# Adafruit_QMC5883P_Magnetometer.net
KiCad netlist of a schematic drawn in EAGLE
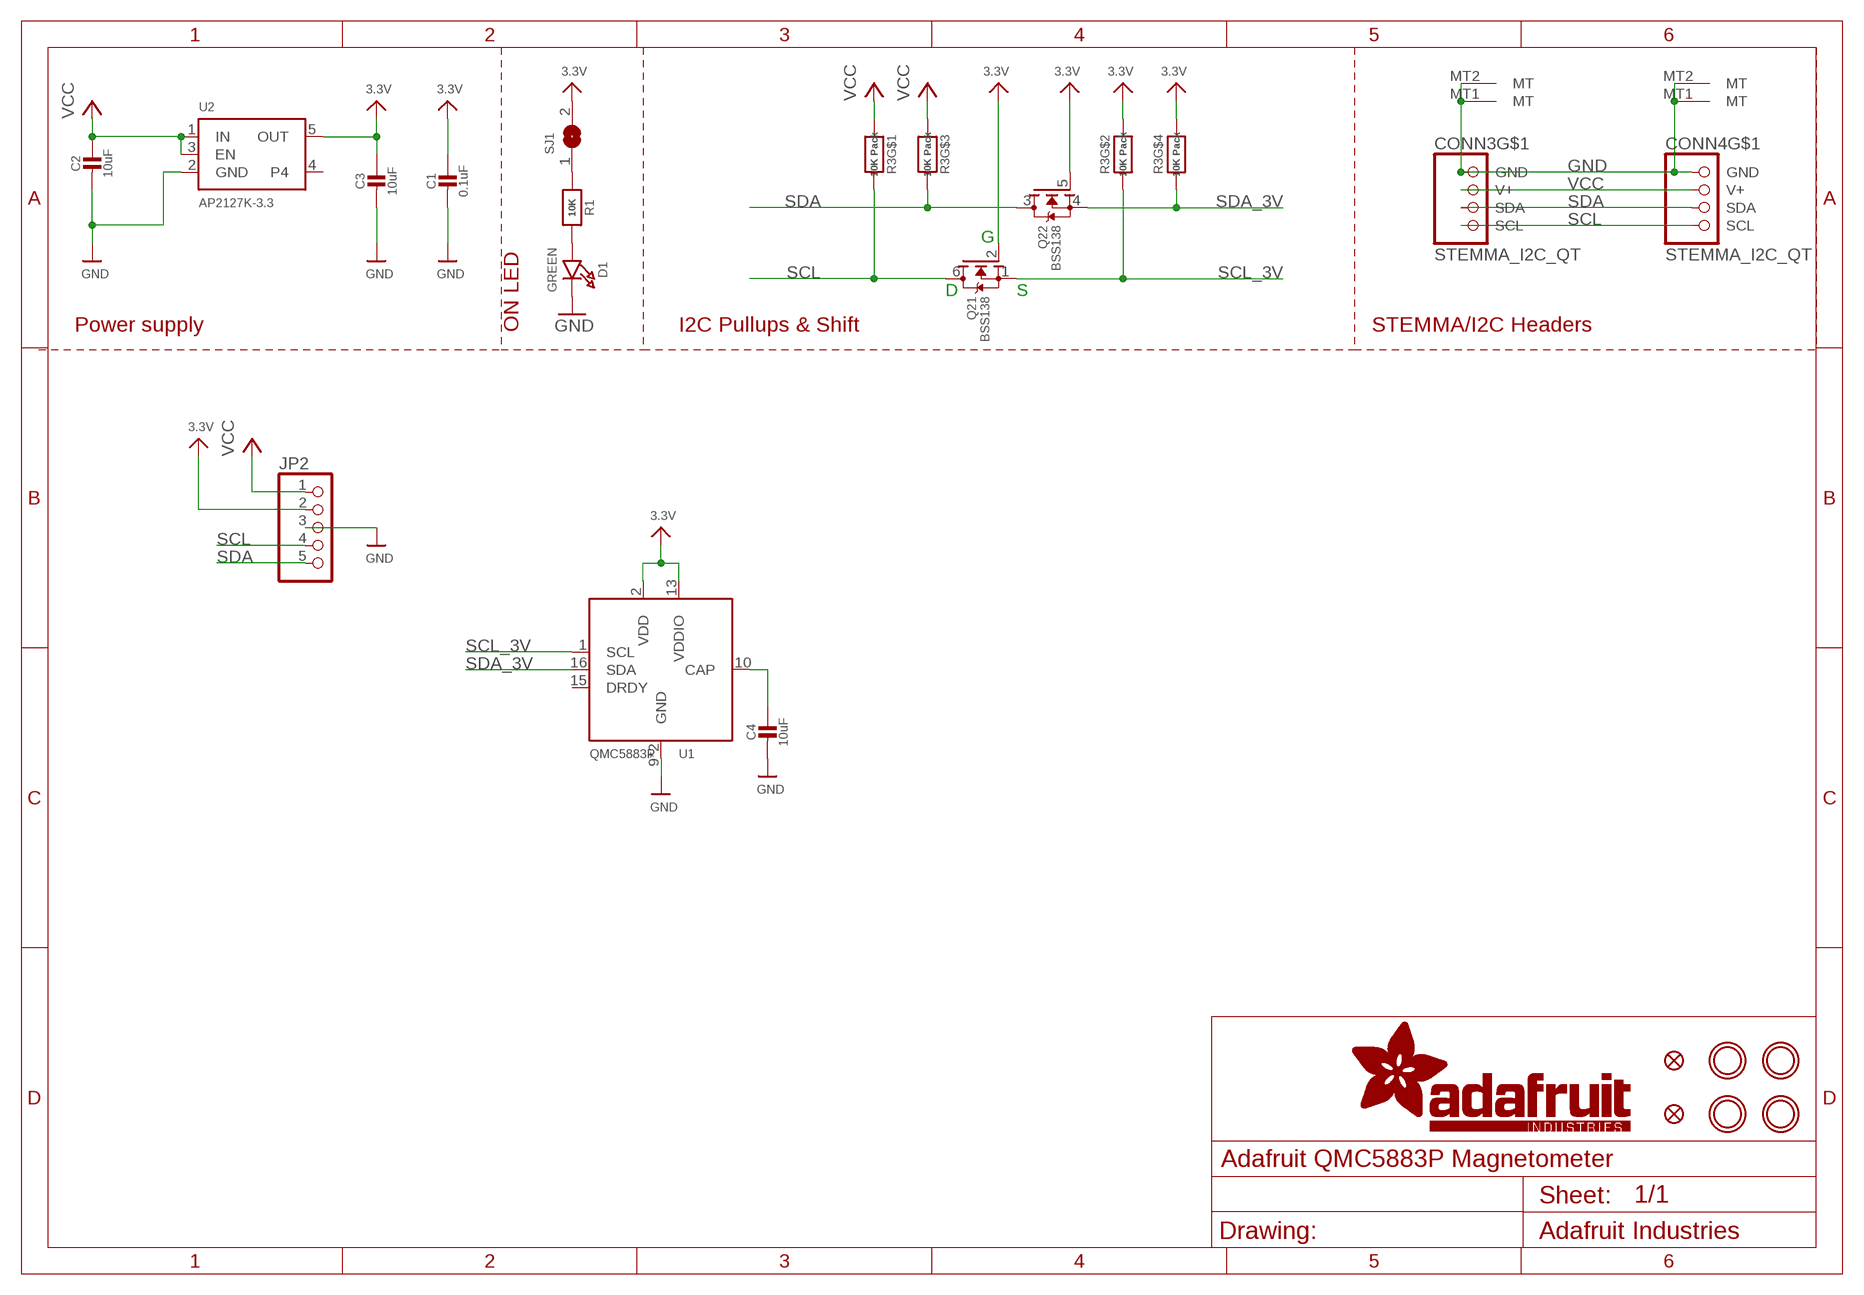
[diagram p0: schematic, sheet 1]

(export (version "E")
  (design (tool "Eeschema 10.0.6"))
  (components
    (comp (ref "C1")
      (value "0.1uF")
      (footprint "eagle-import:0603-NO")
      (libsource (lib "eagle-import") (part "CAP_CERAMIC0603_NO"))
    )
    (comp (ref "C2")
      (value "10uF")
      (footprint "eagle-import:0805-NO")
      (libsource (lib "eagle-import") (part "CAP_CERAMIC0805-NOOUTLINE"))
    )
    (comp (ref "C3")
      (value "10uF")
      (footprint "eagle-import:0805-NO")
      (libsource (lib "eagle-import") (part "CAP_CERAMIC0805-NOOUTLINE"))
    )
    (comp (ref "C4")
      (value "10uF")
      (footprint "eagle-import:0805-NO")
      (libsource (lib "eagle-import") (part "CAP_CERAMIC0805-NOOUTLINE"))
    )
    (comp (ref "CONN3")
      (value "STEMMA_I2C_QT")
      (footprint "eagle-import:JST_SH4")
      (libsource (lib "eagle-import") (part "STEMMA_I2C_QT"))
    )
    (comp (ref "CONN4")
      (value "STEMMA_I2C_QT")
      (footprint "eagle-import:JST_SH4")
      (libsource (lib "eagle-import") (part "STEMMA_I2C_QT"))
    )
    (comp (ref "D1")
      (value "GREEN")
      (footprint "eagle-import:CHIPLED_0603_NOOUTLINE")
      (libsource (lib "eagle-import") (part "LED0603_NOOUTLINE"))
    )
    (comp (ref "FID3")
      (value "FIDUCIAL_0.5MM")
      (footprint "eagle-import:FIDUCIAL_0.5MM")
      (libsource (lib "eagle-import") (part "FIDUCIAL_0.5MM"))
    )
    (comp (ref "FID4")
      (value "FIDUCIAL_0.5MM")
      (footprint "eagle-import:FIDUCIAL_0.5MM")
      (libsource (lib "eagle-import") (part "FIDUCIAL_0.5MM"))
    )
    (comp (ref "JP2")
      (value "HEADER-1X570MIL")
      (footprint "eagle-import:1X05_ROUND_70")
      (libsource (lib "eagle-import") (part "HEADER-1X570MIL"))
    )
    (comp (ref "Q2")
      (value "BSS138")
      (footprint "eagle-import:SOT363")
      (libsource (lib "eagle-import") (part "MOSFET-N_DUAL"))
    )
    (comp (ref "R1")
      (value "10K")
      (footprint "eagle-import:0603-NO")
      (libsource (lib "eagle-import") (part "RESISTOR_0603_NOOUT"))
    )
    (comp (ref "R3")
      (value "10K Pack")
      (footprint "eagle-import:RESPACK_4X0603")
      (libsource (lib "eagle-import") (part "RESISTOR_4PACK"))
    )
    (comp (ref "SJ1")
      (value "SOLDERJUMPERCLOSED")
      (footprint "eagle-import:SOLDERJUMPER_CLOSEDWIRE")
      (libsource (lib "eagle-import") (part "SOLDERJUMPERCLOSED"))
    )
    (comp (ref "U$1")
      (value "MOUNTINGHOLE2.5")
      (footprint "eagle-import:MOUNTINGHOLE_2.5_PLATED")
      (libsource (lib "eagle-import") (part "MOUNTINGHOLE2.5"))
    )
    (comp (ref "U$17")
      (value "MOUNTINGHOLE2.5")
      (footprint "eagle-import:MOUNTINGHOLE_2.5_PLATED")
      (libsource (lib "eagle-import") (part "MOUNTINGHOLE2.5"))
    )
    (comp (ref "U$19")
      (value "MOUNTINGHOLE2.5")
      (footprint "eagle-import:MOUNTINGHOLE_2.5_PLATED")
      (libsource (lib "eagle-import") (part "MOUNTINGHOLE2.5"))
    )
    (comp (ref "U$21")
      (value "MOUNTINGHOLE2.5")
      (footprint "eagle-import:MOUNTINGHOLE_2.5_PLATED")
      (libsource (lib "eagle-import") (part "MOUNTINGHOLE2.5"))
    )
    (comp (ref "U1")
      (value "QMC5883P")
      (footprint "eagle-import:HMC5883L")
      (libsource (lib "eagle-import") (part "MMC5883MA"))
    )
    (comp (ref "U2")
      (value "AP2127K-3.3")
      (footprint "eagle-import:SOT23-5")
      (libsource (lib "eagle-import") (part "VREG_SOT23-5"))
    )
  )
  (nets
    (net (code "1") (name "/SCL") (class "Default")
      (node (ref "CONN3") (pin "4") (pinfunction "SCL_4") (pintype "passive"))
      (node (ref "CONN4") (pin "4") (pinfunction "SCL_4") (pintype "passive"))
      (node (ref "JP2") (pin "4") (pinfunction "4_4") (pintype "passive"))
      (node (ref "Q2") (pin "6") (pinfunction "D_6") (pintype "bidirectional"))
      (node (ref "R3") (pin "8") (pinfunction "2_8") (pintype "passive"))
    )
    (net (code "2") (name "/SCL_3V") (class "Default")
      (node (ref "Q2") (pin "1") (pinfunction "S_1") (pintype "bidirectional"))
      (node (ref "R3") (pin "7") (pinfunction "2_7") (pintype "passive"))
      (node (ref "U1") (pin "1") (pinfunction "SCL_1") (pintype "bidirectional"))
    )
    (net (code "3") (name "/SDA") (class "Default")
      (node (ref "CONN3") (pin "3") (pinfunction "SDA_3") (pintype "passive"))
      (node (ref "CONN4") (pin "3") (pinfunction "SDA_3") (pintype "passive"))
      (node (ref "JP2") (pin "5") (pinfunction "5_5") (pintype "passive"))
      (node (ref "Q2") (pin "3") (pinfunction "D_3") (pintype "bidirectional"))
      (node (ref "R3") (pin "6") (pinfunction "2_6") (pintype "passive"))
    )
    (net (code "4") (name "/SDA_3V") (class "Default")
      (node (ref "Q2") (pin "4") (pinfunction "S_4") (pintype "bidirectional"))
      (node (ref "R3") (pin "5") (pinfunction "2_5") (pintype "passive"))
      (node (ref "U1") (pin "16") (pinfunction "SDA_16") (pintype "bidirectional"))
    )
    (net (code "5") (name "3.3V") (class "Default")
      (node (ref "C1") (pin "1") (pinfunction "1_1") (pintype "passive"))
      (node (ref "C3") (pin "1") (pinfunction "1_1") (pintype "passive"))
      (node (ref "JP2") (pin "2") (pinfunction "2_2") (pintype "passive"))
      (node (ref "Q2") (pin "2") (pinfunction "G_2") (pintype "bidirectional"))
      (node (ref "Q2") (pin "5") (pinfunction "G_5") (pintype "bidirectional"))
      (node (ref "R3") (pin "2") (pinfunction "1_2") (pintype "passive"))
      (node (ref "R3") (pin "4") (pinfunction "1_4") (pintype "passive"))
      (node (ref "SJ1") (pin "2") (pinfunction "2_2") (pintype "passive"))
      (node (ref "U1") (pin "13") (pinfunction "VDDIO_13") (pintype "power_in"))
      (node (ref "U1") (pin "2") (pinfunction "VDD_2") (pintype "power_in"))
      (node (ref "U2") (pin "5") (pinfunction "OUT_5") (pintype "power_in"))
    )
    (net (code "6") (name "GND") (class "Default")
      (node (ref "C1") (pin "2") (pinfunction "2_2") (pintype "passive"))
      (node (ref "C2") (pin "2") (pinfunction "2_2") (pintype "passive"))
      (node (ref "C3") (pin "2") (pinfunction "2_2") (pintype "passive"))
      (node (ref "C4") (pin "2") (pinfunction "2_2") (pintype "passive"))
      (node (ref "CONN3") (pin "1") (pinfunction "GND_1") (pintype "passive"))
      (node (ref "CONN3") (pin "MT1") (pinfunction "MT_MT1") (pintype "bidirectional"))
      (node (ref "CONN3") (pin "MT2") (pinfunction "MT_MT2") (pintype "bidirectional"))
      (node (ref "CONN4") (pin "1") (pinfunction "GND_1") (pintype "passive"))
      (node (ref "CONN4") (pin "MT1") (pinfunction "MT_MT1") (pintype "bidirectional"))
      (node (ref "CONN4") (pin "MT2") (pinfunction "MT_MT2") (pintype "bidirectional"))
      (node (ref "D1") (pin "C") (pinfunction "C_C") (pintype "passive"))
      (node (ref "JP2") (pin "3") (pinfunction "3_3") (pintype "passive"))
      (node (ref "U1") (pin "11") (pinfunction "GND_11") (pintype "power_in"))
      (node (ref "U1") (pin "9") (pinfunction "GND_9") (pintype "power_in"))
      (node (ref "U2") (pin "2") (pinfunction "GND_2") (pintype "power_in"))
    )
    (net (code "7") (name "Net-(D1-PadA)") (class "Default")
      (node (ref "D1") (pin "A") (pinfunction "A_A") (pintype "passive"))
      (node (ref "R1") (pin "2") (pinfunction "2_2") (pintype "passive"))
    )
    (net (code "8") (name "Net-(R1-Pad1)") (class "Default")
      (node (ref "R1") (pin "1") (pinfunction "1_1") (pintype "passive"))
      (node (ref "SJ1") (pin "1") (pinfunction "1_1") (pintype "passive"))
    )
    (net (code "9") (name "Net-(U1-CAP)") (class "Default")
      (node (ref "C4") (pin "1") (pinfunction "1_1") (pintype "passive"))
      (node (ref "U1") (pin "10") (pinfunction "CAP_10") (pintype "input"))
    )
    (net (code "10") (name "VCC") (class "Default")
      (node (ref "C2") (pin "1") (pinfunction "1_1") (pintype "passive"))
      (node (ref "CONN3") (pin "2") (pinfunction "V+_2") (pintype "passive"))
      (node (ref "CONN4") (pin "2") (pinfunction "V+_2") (pintype "passive"))
      (node (ref "JP2") (pin "1") (pinfunction "1_1") (pintype "passive"))
      (node (ref "R3") (pin "1") (pinfunction "1_1") (pintype "passive"))
      (node (ref "R3") (pin "3") (pinfunction "1_3") (pintype "passive"))
      (node (ref "U2") (pin "1") (pinfunction "IN_1") (pintype "power_in"))
      (node (ref "U2") (pin "3") (pinfunction "EN_3") (pintype "input"))
    )
    (net (code "11") (name "unconnected-(U1-DRDY-Pad15)") (class "Default")
      (node (ref "U1") (pin "15") (pinfunction "DRDY_15") (pintype "output"))
    )
    (net (code "12") (name "unconnected-(U2-P4-Pad4)") (class "Default")
      (node (ref "U2") (pin "4") (pinfunction "P4_4") (pintype "bidirectional"))
    )
  )
)
